# Rauchmelder_2_1c.net
KiCad netlist of a schematic drawn in EAGLE
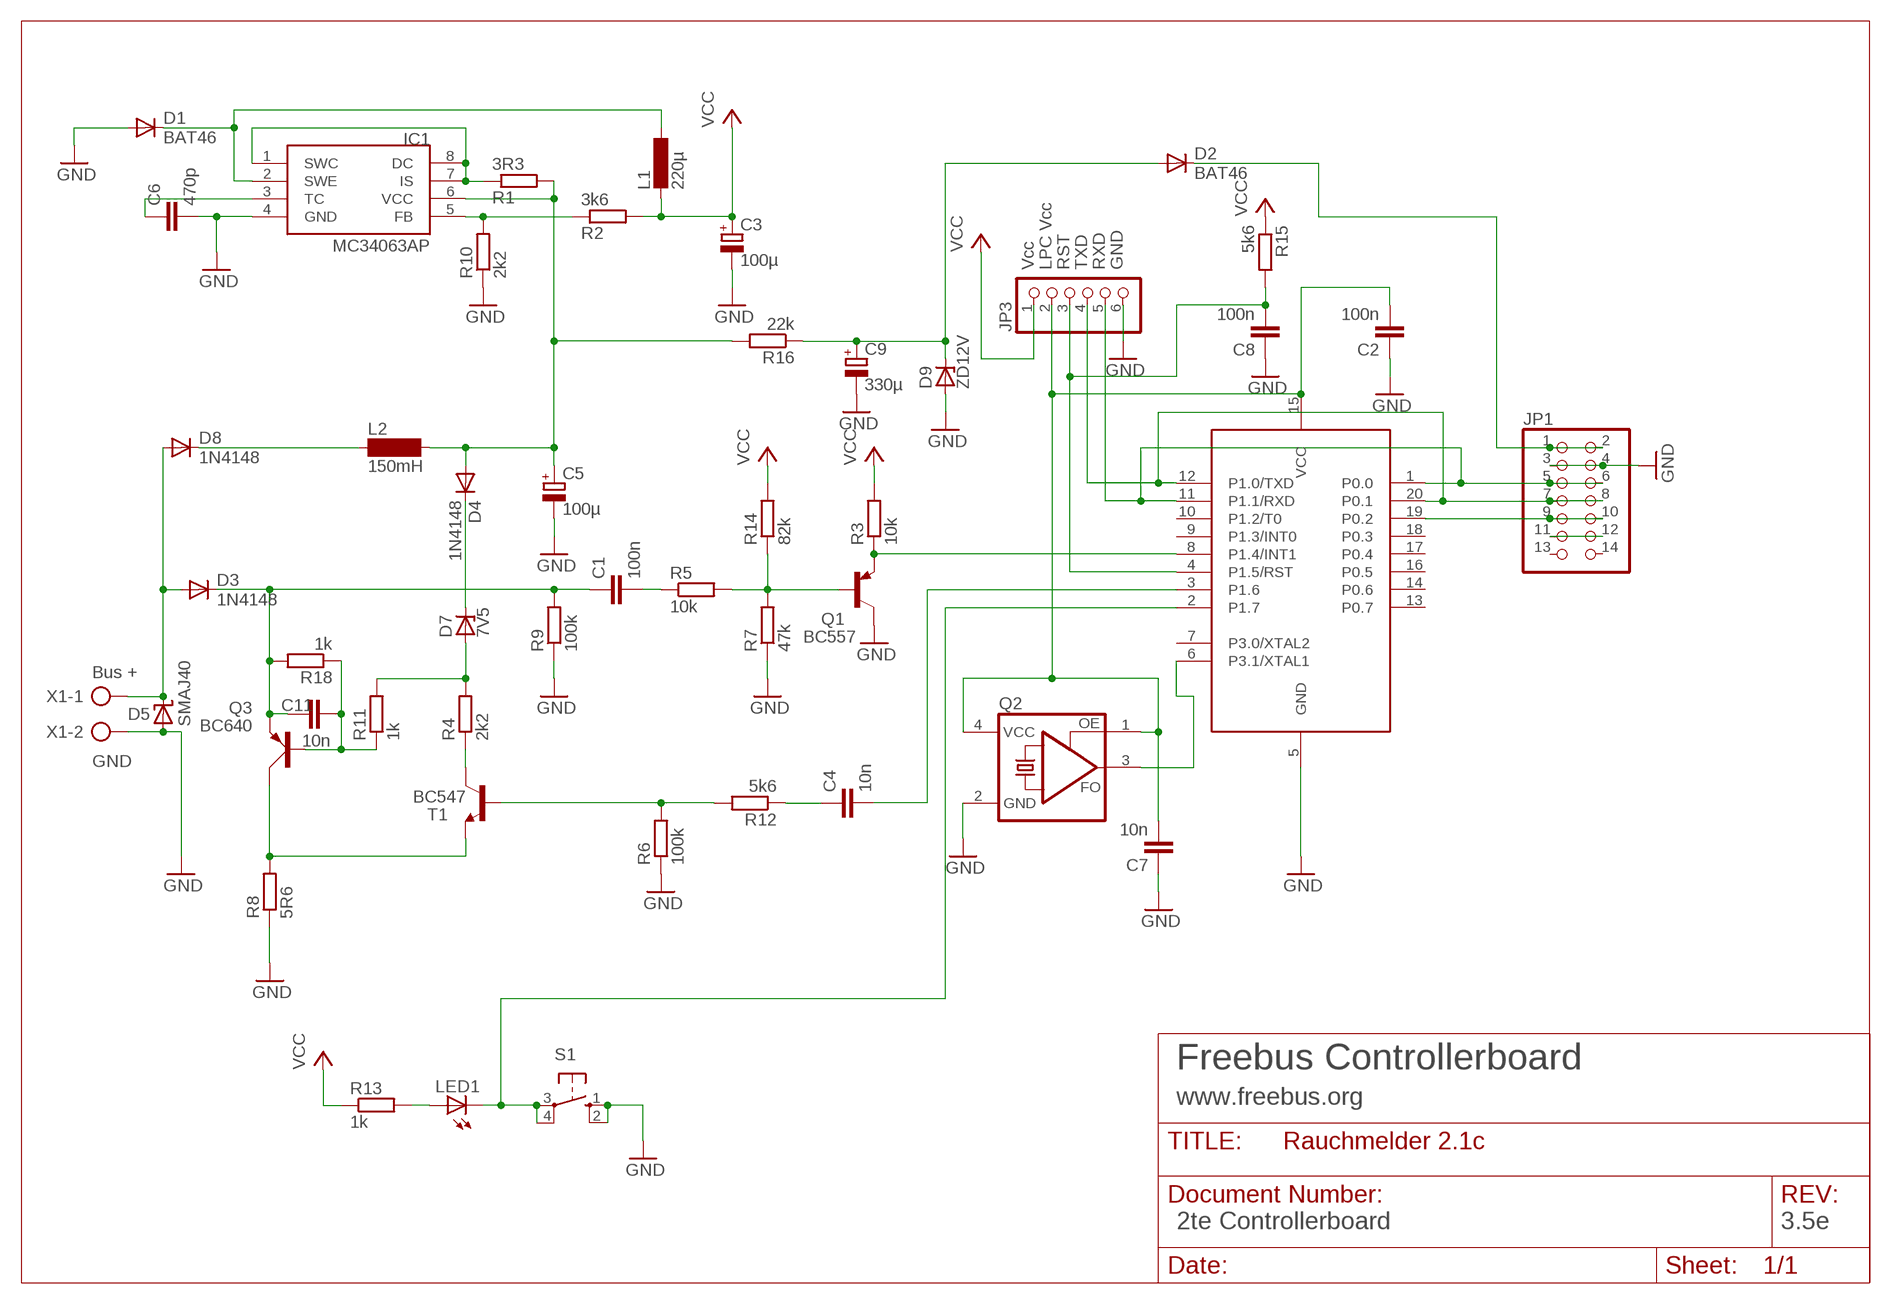
[diagram p0: schematic, sheet 1]

(export (version "E")
  (design (tool "Eeschema 10.0.6"))
  (components
    (comp (ref "89LPC922")
      (value "89LPC922")
      (footprint "eagle-import:DIL20")
      (libsource (lib "eagle-import") (part "89LPC922"))
    )
    (comp (ref "C1")
      (value "100n")
      (footprint "eagle-import:C025-024X044")
      (libsource (lib "eagle-import") (part "C-EU025-024X044"))
    )
    (comp (ref "C2")
      (value "100n")
      (footprint "eagle-import:C025-024X044")
      (libsource (lib "eagle-import") (part "C-EU025-024X044"))
    )
    (comp (ref "C3")
      (value "100µ")
      (footprint "eagle-import:E2,5-6")
      (libsource (lib "eagle-import") (part "CPOL-EUE2.5-6"))
    )
    (comp (ref "C4")
      (value "10n")
      (footprint "eagle-import:C025-024X044")
      (libsource (lib "eagle-import") (part "C-EU025-024X044"))
    )
    (comp (ref "C5")
      (value "100µ")
      (footprint "eagle-import:E3,5-8")
      (libsource (lib "eagle-import") (part "CPOL-EUE3.5-8"))
    )
    (comp (ref "C6")
      (value "470p")
      (footprint "eagle-import:C025-024X044")
      (libsource (lib "eagle-import") (part "C-EU025-024X044"))
    )
    (comp (ref "C7")
      (value "10n")
      (footprint "eagle-import:C1206")
      (libsource (lib "eagle-import") (part "C-EUC1206"))
    )
    (comp (ref "C8")
      (value "100n")
      (footprint "eagle-import:C025-024X044")
      (libsource (lib "eagle-import") (part "C-EU025-024X044"))
    )
    (comp (ref "C9")
      (value "330µ")
      (footprint "eagle-import:E3,5-8")
      (libsource (lib "eagle-import") (part "CPOL-EUE3.5-8"))
    )
    (comp (ref "C11")
      (value "10n")
      (footprint "eagle-import:C025-024X044")
      (libsource (lib "eagle-import") (part "C-EU025-024X044"))
    )
    (comp (ref "D1")
      (value "BAT46")
      (footprint "eagle-import:DO34-7")
      (libsource (lib "eagle-import") (part "BAT81"))
    )
    (comp (ref "D2")
      (value "BAT46")
      (footprint "eagle-import:DO34-7")
      (libsource (lib "eagle-import") (part "BAT81"))
    )
    (comp (ref "D3")
      (value "1N4148")
      (footprint "eagle-import:DO35-10")
      (libsource (lib "eagle-import") (part "1N4148"))
    )
    (comp (ref "D4")
      (value "1N4148")
      (footprint "eagle-import:DO35-10")
      (libsource (lib "eagle-import") (part "1N4148"))
    )
    (comp (ref "D5")
      (value "SMAJ40")
      (footprint "eagle-import:SMBJ")
      (libsource (lib "eagle-import") (part "SUPPRESSOR-SMBJ"))
    )
    (comp (ref "D7")
      (value "7V5")
      (footprint "eagle-import:ZDIO-2.5")
      (libsource (lib "eagle-import") (part "BZX85ZDIOV"))
    )
    (comp (ref "D8")
      (value "1N4148")
      (footprint "eagle-import:D-7.5")
      (libsource (lib "eagle-import") (part "DIODE-D-7.5"))
    )
    (comp (ref "D9")
      (value "ZD12V")
      (footprint "eagle-import:DO34Z7")
      (libsource (lib "eagle-import") (part "BZX90"))
    )
    (comp (ref "IC1")
      (value "MC34063AP")
      (footprint "eagle-import:DIL08")
      (libsource (lib "eagle-import") (part "MC34063AP"))
    )
    (comp (ref "JP1")
      (value "PINHD-2X7")
      (footprint "eagle-import:2X07")
      (libsource (lib "eagle-import") (part "PINHD-2X7"))
    )
    (comp (ref "JP3")
      (value "PINHD-1X6")
      (footprint "eagle-import:1X06")
      (libsource (lib "eagle-import") (part "PINHD-1X6"))
    )
    (comp (ref "L1")
      (value "220µ")
      (footprint "eagle-import:0207_12")
      (libsource (lib "eagle-import") (part "L-EU0207/12"))
    )
    (comp (ref "L2")
      (value "150mH")
      (footprint "eagle-import:BS11")
      (libsource (lib "eagle-import") (part "BS11"))
    )
    (comp (ref "LED1")
      (value "LED3MM")
      (footprint "eagle-import:LED3MM")
      (libsource (lib "eagle-import") (part "LED3MM"))
    )
    (comp (ref "Q1")
      (value "BC557")
      (footprint "eagle-import:TO92")
      (libsource (lib "eagle-import") (part "BC557"))
    )
    (comp (ref "Q2")
      (value "ASFL")
      (footprint "eagle-import:ASF")
      (libsource (lib "eagle-import") (part "ASFL"))
    )
    (comp (ref "Q3")
      (value "BC640")
      (footprint "eagle-import:SOT54D")
      (libsource (lib "eagle-import") (part "BC640"))
    )
    (comp (ref "R1")
      (value "3R3")
      (footprint "eagle-import:0207_7")
      (libsource (lib "eagle-import") (part "R-EU_0207/7"))
    )
    (comp (ref "R2")
      (value "3k6")
      (footprint "eagle-import:0207_7")
      (libsource (lib "eagle-import") (part "R-EU_0207/7"))
    )
    (comp (ref "R3")
      (value "10k")
      (footprint "eagle-import:0207_7")
      (libsource (lib "eagle-import") (part "R-EU_0207/7"))
    )
    (comp (ref "R4")
      (value "2k2")
      (footprint "eagle-import:0207_2V")
      (libsource (lib "eagle-import") (part "R-EU_0207/2V"))
    )
    (comp (ref "R5")
      (value "10k")
      (footprint "eagle-import:0207_7")
      (libsource (lib "eagle-import") (part "R-EU_0207/7"))
    )
    (comp (ref "R6")
      (value "100k")
      (footprint "eagle-import:0207_2V")
      (libsource (lib "eagle-import") (part "R-EU_0207/2V"))
    )
    (comp (ref "R7")
      (value "47k")
      (footprint "eagle-import:0207_7")
      (libsource (lib "eagle-import") (part "R-EU_0207/7"))
    )
    (comp (ref "R8")
      (value "5R6")
      (footprint "eagle-import:0207_2V")
      (libsource (lib "eagle-import") (part "R-EU_0207/2V"))
    )
    (comp (ref "R9")
      (value "100k")
      (footprint "eagle-import:0207_7")
      (libsource (lib "eagle-import") (part "R-EU_0207/7"))
    )
    (comp (ref "R10")
      (value "2k2")
      (footprint "eagle-import:0207_7")
      (libsource (lib "eagle-import") (part "R-EU_0207/7"))
    )
    (comp (ref "R11")
      (value "1k")
      (footprint "eagle-import:0207_2V")
      (libsource (lib "eagle-import") (part "R-EU_0207/2V"))
    )
    (comp (ref "R12")
      (value "5k6")
      (footprint "eagle-import:0207_7")
      (libsource (lib "eagle-import") (part "R-EU_0207/7"))
    )
    (comp (ref "R13")
      (value "1k")
      (footprint "eagle-import:0207_7")
      (libsource (lib "eagle-import") (part "R-EU_0207/7"))
    )
    (comp (ref "R14")
      (value "82k")
      (footprint "eagle-import:0207_7")
      (libsource (lib "eagle-import") (part "R-EU_0207/7"))
    )
    (comp (ref "R15")
      (value "5k6")
      (footprint "eagle-import:0207_2V")
      (libsource (lib "eagle-import") (part "R-EU_0207/2V"))
    )
    (comp (ref "R16")
      (value "22k")
      (footprint "eagle-import:0207_2V")
      (libsource (lib "eagle-import") (part "R-EU_0207/2V"))
    )
    (comp (ref "R18")
      (value "1k")
      (footprint "eagle-import:0207_2V")
      (libsource (lib "eagle-import") (part "R-EU_0207/2V"))
    )
    (comp (ref "S1")
      (value "10-XX")
      (footprint "eagle-import:B3F-10XX")
      (libsource (lib "eagle-import") (part "10-XX"))
    )
    (comp (ref "T1")
      (value "BC547")
      (footprint "eagle-import:TO92")
      (libsource (lib "eagle-import") (part "BC547"))
    )
    (comp (ref "X1")
      (value "AK500/2")
      (footprint "eagle-import:AK500_2")
      (libsource (lib "eagle-import") (part "AK500/2"))
    )
  )
  (nets
    (net (code "1") (name "GND") (class "Default")
      (node (ref "89LPC922") (pin "5") (pinfunction "GND_5") (pintype "bidirectional"))
      (node (ref "C2") (pin "1") (pinfunction "1_1") (pintype "passive"))
      (node (ref "C3") (pin "-") (pinfunction "-_-") (pintype "passive"))
      (node (ref "C5") (pin "-") (pinfunction "-_-") (pintype "passive"))
      (node (ref "C6") (pin "2") (pinfunction "2_2") (pintype "passive"))
      (node (ref "C7") (pin "1") (pinfunction "1_1") (pintype "passive"))
      (node (ref "C8") (pin "1") (pinfunction "1_1") (pintype "passive"))
      (node (ref "C9") (pin "-") (pinfunction "-_-") (pintype "passive"))
      (node (ref "D1") (pin "A") (pinfunction "A_A") (pintype "passive"))
      (node (ref "D5") (pin "A") (pinfunction "A_A") (pintype "passive"))
      (node (ref "D9") (pin "A") (pinfunction "A_A") (pintype "passive"))
      (node (ref "IC1") (pin "4") (pinfunction "GND_4") (pintype "passive"))
      (node (ref "JP1") (pin "3") (pinfunction "3_3") (pintype "passive"))
      (node (ref "JP1") (pin "4") (pinfunction "4_4") (pintype "passive"))
      (node (ref "JP3") (pin "6") (pinfunction "6_6") (pintype "passive"))
      (node (ref "Q1") (pin "3") (pinfunction "C_3") (pintype "passive"))
      (node (ref "Q2") (pin "2") (pinfunction "GND_2") (pintype "power_in"))
      (node (ref "R10") (pin "1") (pinfunction "1_1") (pintype "passive"))
      (node (ref "R6") (pin "1") (pinfunction "1_1") (pintype "passive"))
      (node (ref "R7") (pin "1") (pinfunction "1_1") (pintype "passive"))
      (node (ref "R8") (pin "1") (pinfunction "1_1") (pintype "passive"))
      (node (ref "R9") (pin "1") (pinfunction "1_1") (pintype "passive"))
      (node (ref "S1") (pin "1") (pinfunction "S_1") (pintype "passive"))
      (node (ref "S1") (pin "2") (pinfunction "S1_2") (pintype "passive"))
      (node (ref "X1") (pin "2") (pinfunction "KL_2") (pintype "passive"))
    )
    (net (code "2") (name "Net-(89LPC922-P0.0)") (class "Default")
      (node (ref "89LPC922") (pin "1") (pinfunction "P0.0_1") (pintype "bidirectional"))
      (node (ref "89LPC922") (pin "11") (pinfunction "P1.1/RXD_11") (pintype "bidirectional"))
      (node (ref "JP1") (pin "5") (pinfunction "5_5") (pintype "passive"))
      (node (ref "JP1") (pin "6") (pinfunction "6_6") (pintype "passive"))
      (node (ref "JP3") (pin "5") (pinfunction "5_5") (pintype "passive"))
    )
    (net (code "3") (name "Net-(89LPC922-P0.1)") (class "Default")
      (node (ref "89LPC922") (pin "12") (pinfunction "P1.0/TXD_12") (pintype "bidirectional"))
      (node (ref "89LPC922") (pin "20") (pinfunction "P0.1_20") (pintype "bidirectional"))
      (node (ref "JP1") (pin "7") (pinfunction "7_7") (pintype "passive"))
      (node (ref "JP1") (pin "8") (pinfunction "8_8") (pintype "passive"))
      (node (ref "JP3") (pin "4") (pinfunction "4_4") (pintype "passive"))
    )
    (net (code "4") (name "Net-(89LPC922-P0.2)") (class "Default")
      (node (ref "89LPC922") (pin "19") (pinfunction "P0.2_19") (pintype "bidirectional"))
      (node (ref "JP1") (pin "10") (pinfunction "10_10") (pintype "passive"))
      (node (ref "JP1") (pin "9") (pinfunction "9_9") (pintype "passive"))
    )
    (net (code "5") (name "Net-(89LPC922-P1.4{slash}INT1)") (class "Default")
      (node (ref "89LPC922") (pin "8") (pinfunction "P1.4/INT1_8") (pintype "bidirectional"))
      (node (ref "Q1") (pin "1") (pinfunction "E_1") (pintype "passive"))
      (node (ref "R3") (pin "1") (pinfunction "1_1") (pintype "passive"))
    )
    (net (code "6") (name "Net-(89LPC922-P1.5{slash}RST)") (class "Default")
      (node (ref "89LPC922") (pin "4") (pinfunction "P1.5/RST_4") (pintype "bidirectional"))
      (node (ref "C8") (pin "2") (pinfunction "2_2") (pintype "passive"))
      (node (ref "JP3") (pin "3") (pinfunction "3_3") (pintype "passive"))
      (node (ref "R15") (pin "2") (pinfunction "2_2") (pintype "passive"))
    )
    (net (code "7") (name "Net-(89LPC922-P1.6)") (class "Default")
      (node (ref "89LPC922") (pin "3") (pinfunction "P1.6_3") (pintype "bidirectional"))
      (node (ref "C4") (pin "2") (pinfunction "2_2") (pintype "passive"))
    )
    (net (code "8") (name "Net-(89LPC922-P1.7)") (class "Default")
      (node (ref "89LPC922") (pin "2") (pinfunction "P1.7_2") (pintype "bidirectional"))
      (node (ref "LED1") (pin "K") (pinfunction "C_K") (pintype "passive"))
      (node (ref "S1") (pin "3") (pinfunction "P_3") (pintype "passive"))
      (node (ref "S1") (pin "4") (pinfunction "P1_4") (pintype "passive"))
    )
    (net (code "9") (name "Net-(89LPC922-P3.1{slash}XTAL1)") (class "Default")
      (node (ref "89LPC922") (pin "6") (pinfunction "P3.1/XTAL1_6") (pintype "bidirectional"))
      (node (ref "Q2") (pin "3") (pinfunction "FO_3") (pintype "output"))
    )
    (net (code "10") (name "Net-(89LPC922-VCC)") (class "Default")
      (node (ref "89LPC922") (pin "15") (pinfunction "VCC_15") (pintype "bidirectional"))
      (node (ref "C2") (pin "2") (pinfunction "2_2") (pintype "passive"))
      (node (ref "C7") (pin "2") (pinfunction "2_2") (pintype "passive"))
      (node (ref "JP3") (pin "2") (pinfunction "2_2") (pintype "passive"))
      (node (ref "Q2") (pin "1") (pinfunction "OE_1") (pintype "input"))
      (node (ref "Q2") (pin "4") (pinfunction "VCC_4") (pintype "power_in"))
    )
    (net (code "11") (name "Net-(C1-Pad1)") (class "Default")
      (node (ref "C1") (pin "1") (pinfunction "1_1") (pintype "passive"))
      (node (ref "C11") (pin "1") (pinfunction "1_1") (pintype "passive"))
      (node (ref "D3") (pin "C") (pinfunction "C_C") (pintype "passive"))
      (node (ref "Q3") (pin "E") (pinfunction "E_E") (pintype "passive"))
      (node (ref "R18") (pin "2") (pinfunction "2_2") (pintype "passive"))
      (node (ref "R9") (pin "2") (pinfunction "2_2") (pintype "passive"))
    )
    (net (code "12") (name "Net-(C1-Pad2)") (class "Default")
      (node (ref "C1") (pin "2") (pinfunction "2_2") (pintype "passive"))
      (node (ref "R5") (pin "1") (pinfunction "1_1") (pintype "passive"))
    )
    (net (code "13") (name "Net-(C4-Pad1)") (class "Default")
      (node (ref "C4") (pin "1") (pinfunction "1_1") (pintype "passive"))
      (node (ref "R12") (pin "1") (pinfunction "1_1") (pintype "passive"))
    )
    (net (code "14") (name "Net-(C9-Pad+)") (class "Default")
      (node (ref "C9") (pin "+") (pinfunction "+_+") (pintype "passive"))
      (node (ref "D2") (pin "A") (pinfunction "A_A") (pintype "passive"))
      (node (ref "D9") (pin "C") (pinfunction "C_C") (pintype "passive"))
      (node (ref "R16") (pin "1") (pinfunction "1_1") (pintype "passive"))
    )
    (net (code "15") (name "Net-(C11-Pad2)") (class "Default")
      (node (ref "C11") (pin "2") (pinfunction "2_2") (pintype "passive"))
      (node (ref "Q3") (pin "B") (pinfunction "B_B") (pintype "passive"))
      (node (ref "R11") (pin "1") (pinfunction "1_1") (pintype "passive"))
      (node (ref "R18") (pin "1") (pinfunction "1_1") (pintype "passive"))
    )
    (net (code "16") (name "Net-(D2-PadC)") (class "Default")
      (node (ref "D2") (pin "C") (pinfunction "C_C") (pintype "passive"))
      (node (ref "JP1") (pin "1") (pinfunction "1_1") (pintype "passive"))
      (node (ref "JP1") (pin "2") (pinfunction "2_2") (pintype "passive"))
    )
    (net (code "17") (name "Net-(D4-PadC)") (class "Default")
      (node (ref "D4") (pin "C") (pinfunction "C_C") (pintype "passive"))
      (node (ref "D7") (pin "C") (pinfunction "C_C") (pintype "passive"))
    )
    (net (code "18") (name "Net-(D7-PadA)") (class "Default")
      (node (ref "D7") (pin "A") (pinfunction "A_A") (pintype "passive"))
      (node (ref "R11") (pin "2") (pinfunction "2_2") (pintype "passive"))
      (node (ref "R4") (pin "2") (pinfunction "2_2") (pintype "passive"))
    )
    (net (code "19") (name "Net-(D8-PadC)") (class "Default")
      (node (ref "D8") (pin "C") (pinfunction "C_C") (pintype "passive"))
      (node (ref "L2") (pin "1") (pinfunction "1_1") (pintype "passive"))
    )
    (net (code "20") (name "Net-(IC1-DC)") (class "Default")
      (node (ref "IC1") (pin "1") (pinfunction "SWC_1") (pintype "passive"))
      (node (ref "IC1") (pin "7") (pinfunction "IS_7") (pintype "passive"))
      (node (ref "IC1") (pin "8") (pinfunction "DC_8") (pintype "passive"))
      (node (ref "R1") (pin "1") (pinfunction "1_1") (pintype "passive"))
    )
    (net (code "21") (name "Net-(IC1-FB)") (class "Default")
      (node (ref "IC1") (pin "5") (pinfunction "FB_5") (pintype "passive"))
      (node (ref "R10") (pin "2") (pinfunction "2_2") (pintype "passive"))
      (node (ref "R2") (pin "1") (pinfunction "1_1") (pintype "passive"))
    )
    (net (code "22") (name "Net-(IC1-SWE)") (class "Default")
      (node (ref "D1") (pin "C") (pinfunction "C_C") (pintype "passive"))
      (node (ref "IC1") (pin "2") (pinfunction "SWE_2") (pintype "passive"))
      (node (ref "L1") (pin "1") (pinfunction "1_1") (pintype "passive"))
    )
    (net (code "23") (name "Net-(IC1-TC)") (class "Default")
      (node (ref "C6") (pin "1") (pinfunction "1_1") (pintype "passive"))
      (node (ref "IC1") (pin "3") (pinfunction "TC_3") (pintype "passive"))
    )
    (net (code "24") (name "Net-(IC1-VCC)") (class "Default")
      (node (ref "C5") (pin "+") (pinfunction "+_+") (pintype "passive"))
      (node (ref "D4") (pin "A") (pinfunction "A_A") (pintype "passive"))
      (node (ref "IC1") (pin "6") (pinfunction "VCC_6") (pintype "passive"))
      (node (ref "L2") (pin "2") (pinfunction "2_2") (pintype "passive"))
      (node (ref "R1") (pin "2") (pinfunction "2_2") (pintype "passive"))
      (node (ref "R16") (pin "2") (pinfunction "2_2") (pintype "passive"))
    )
    (net (code "25") (name "Net-(JP1-Pad11)") (class "Default")
      (node (ref "JP1") (pin "11") (pinfunction "11_11") (pintype "passive"))
      (node (ref "JP1") (pin "12") (pinfunction "12_12") (pintype "passive"))
    )
    (net (code "26") (name "Net-(LED1-PadA)") (class "Default")
      (node (ref "LED1") (pin "A") (pinfunction "A_A") (pintype "passive"))
      (node (ref "R13") (pin "2") (pinfunction "2_2") (pintype "passive"))
    )
    (net (code "27") (name "Net-(Q1-B)") (class "Default")
      (node (ref "Q1") (pin "2") (pinfunction "B_2") (pintype "passive"))
      (node (ref "R14") (pin "1") (pinfunction "1_1") (pintype "passive"))
      (node (ref "R5") (pin "2") (pinfunction "2_2") (pintype "passive"))
      (node (ref "R7") (pin "2") (pinfunction "2_2") (pintype "passive"))
    )
    (net (code "28") (name "Net-(T1-B)") (class "Default")
      (node (ref "R12") (pin "2") (pinfunction "2_2") (pintype "passive"))
      (node (ref "R6") (pin "2") (pinfunction "2_2") (pintype "passive"))
      (node (ref "T1") (pin "2") (pinfunction "B_2") (pintype "passive"))
    )
    (net (code "29") (name "Net-(T1-C)") (class "Default")
      (node (ref "R4") (pin "1") (pinfunction "1_1") (pintype "passive"))
      (node (ref "T1") (pin "3") (pinfunction "C_3") (pintype "passive"))
    )
    (net (code "30") (name "Net-(T1-E)") (class "Default")
      (node (ref "Q3") (pin "C") (pinfunction "C_C") (pintype "passive"))
      (node (ref "R8") (pin "2") (pinfunction "2_2") (pintype "passive"))
      (node (ref "T1") (pin "1") (pinfunction "E_1") (pintype "passive"))
    )
    (net (code "31") (name "Net-(X1A-KL)") (class "Default")
      (node (ref "D3") (pin "A") (pinfunction "A_A") (pintype "passive"))
      (node (ref "D5") (pin "C") (pinfunction "C_C") (pintype "passive"))
      (node (ref "D8") (pin "A") (pinfunction "A_A") (pintype "passive"))
      (node (ref "X1") (pin "1") (pinfunction "KL_1") (pintype "passive"))
    )
    (net (code "32") (name "VCC") (class "Default")
      (node (ref "C3") (pin "+") (pinfunction "+_+") (pintype "passive"))
      (node (ref "JP3") (pin "1") (pinfunction "1_1") (pintype "passive"))
      (node (ref "L1") (pin "2") (pinfunction "2_2") (pintype "passive"))
      (node (ref "R13") (pin "1") (pinfunction "1_1") (pintype "passive"))
      (node (ref "R14") (pin "2") (pinfunction "2_2") (pintype "passive"))
      (node (ref "R15") (pin "1") (pinfunction "1_1") (pintype "passive"))
      (node (ref "R2") (pin "2") (pinfunction "2_2") (pintype "passive"))
      (node (ref "R3") (pin "2") (pinfunction "2_2") (pintype "passive"))
    )
    (net (code "33") (name "unconnected-(89LPC922-P0.3-Pad18)") (class "Default")
      (node (ref "89LPC922") (pin "18") (pinfunction "P0.3_18") (pintype "bidirectional"))
    )
    (net (code "34") (name "unconnected-(89LPC922-P0.4-Pad17)") (class "Default")
      (node (ref "89LPC922") (pin "17") (pinfunction "P0.4_17") (pintype "bidirectional"))
    )
    (net (code "35") (name "unconnected-(89LPC922-P0.5-Pad16)") (class "Default")
      (node (ref "89LPC922") (pin "16") (pinfunction "P0.5_16") (pintype "bidirectional"))
    )
    (net (code "36") (name "unconnected-(89LPC922-P0.6-Pad14)") (class "Default")
      (node (ref "89LPC922") (pin "14") (pinfunction "P0.6_14") (pintype "bidirectional"))
    )
    (net (code "37") (name "unconnected-(89LPC922-P0.7-Pad13)") (class "Default")
      (node (ref "89LPC922") (pin "13") (pinfunction "P0.7_13") (pintype "bidirectional"))
    )
    (net (code "38") (name "unconnected-(89LPC922-P1.2{slash}T0-Pad10)") (class "Default")
      (node (ref "89LPC922") (pin "10") (pinfunction "P1.2/T0_10") (pintype "bidirectional"))
    )
    (net (code "39") (name "unconnected-(89LPC922-P1.3{slash}INT0-Pad9)") (class "Default")
      (node (ref "89LPC922") (pin "9") (pinfunction "P1.3/INT0_9") (pintype "bidirectional"))
    )
    (net (code "40") (name "unconnected-(89LPC922-P3.0{slash}XTAL2-Pad7)") (class "Default")
      (node (ref "89LPC922") (pin "7") (pinfunction "P3.0/XTAL2_7") (pintype "bidirectional"))
    )
    (net (code "41") (name "unconnected-(JP1-Pad13)") (class "Default")
      (node (ref "JP1") (pin "13") (pinfunction "13_13") (pintype "passive"))
    )
    (net (code "42") (name "unconnected-(JP1-Pad14)") (class "Default")
      (node (ref "JP1") (pin "14") (pinfunction "14_14") (pintype "passive"))
    )
  )
)
